# SCH_The-Weather-Station_2024-06-20.net
KiCad netlist of a schematic drawn in EasyEDA
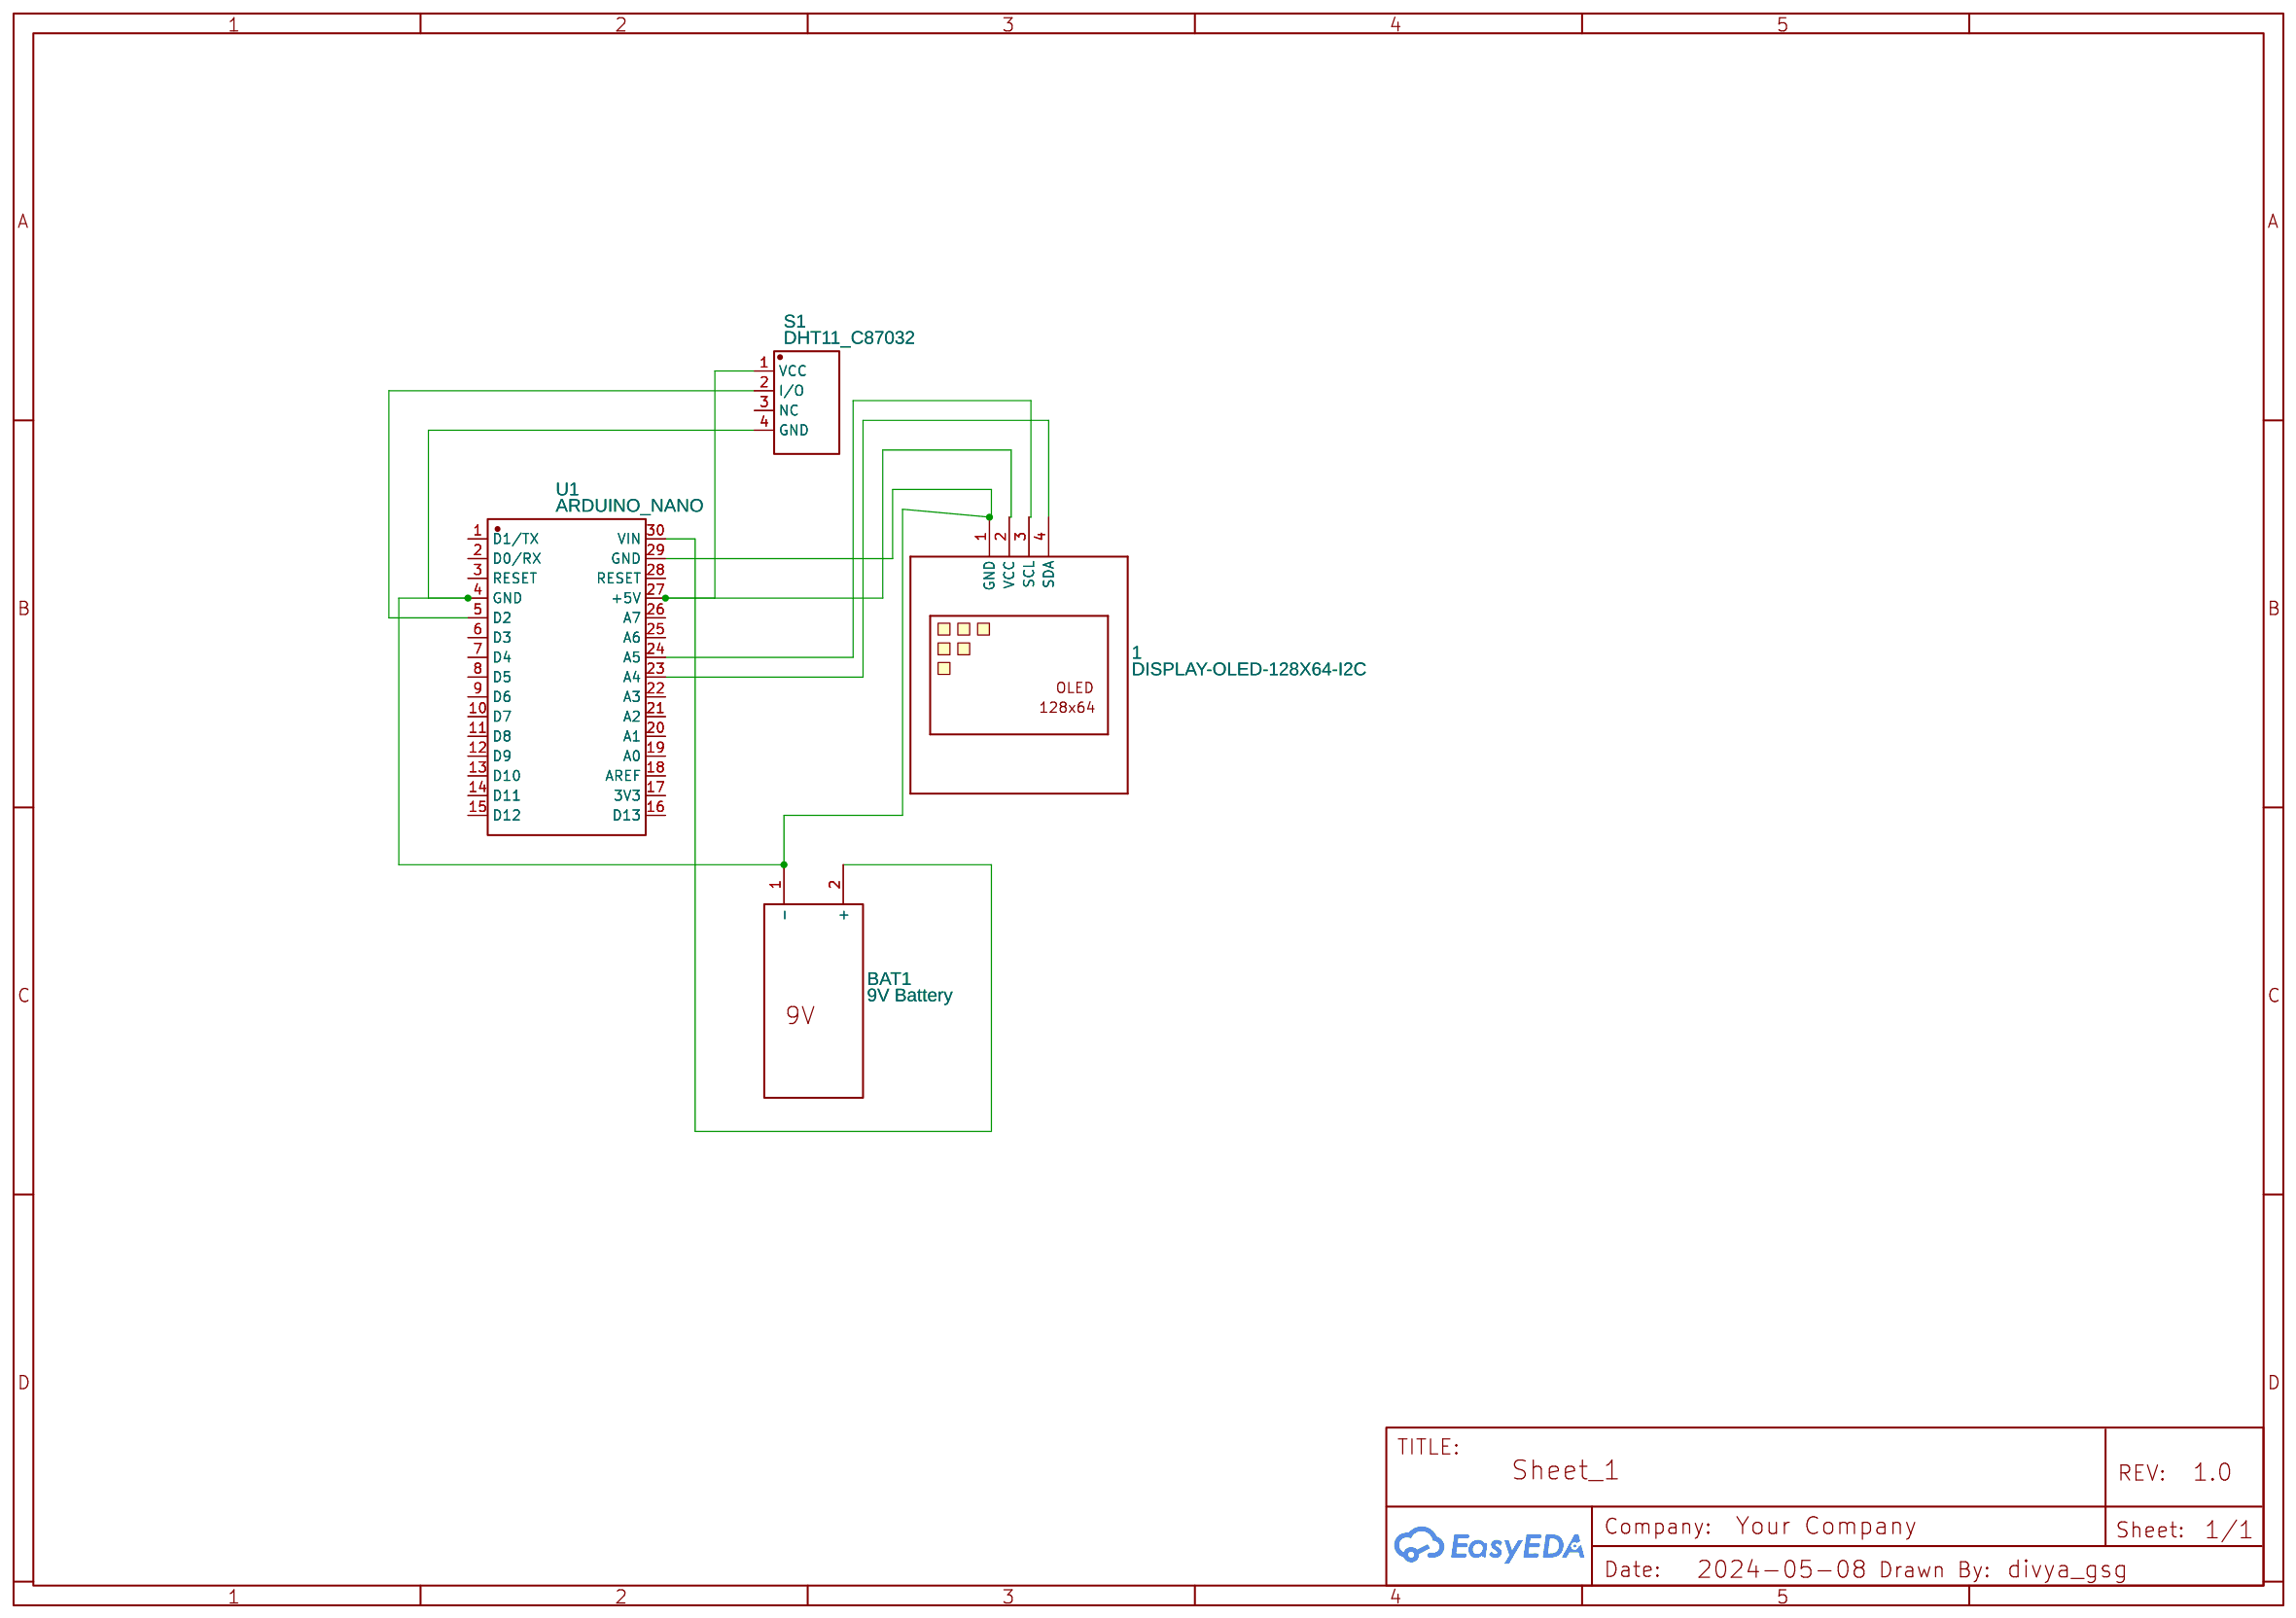
[diagram p0: schematic sheet]

(export (version "E")
  (design (tool "Eeschema 10.0.6"))
  (components
    (comp (ref "1") (value "DISPLAY-OLED-128X64-I2C") (libsource (lib "") (part "DISPLAY-OLED-128X64-I2C")))
    (comp (ref "BAT1") (value "9V Battery") (libsource (lib "") (part "9V Battery")))
    (comp (ref "S1")
      (value "DHT11_C87032")
      (fields (field (name "Manufacturer Part") "DHT11") (field (name "Manufacturer") "AOSONG"))
      (libsource (lib "") (part "DHT11_C87032"))
    )
    (comp (ref "U1") (value "ARDUINO_NANO") (libsource (lib "") (part "ARDUINO_NANO")))
  )
  (nets
    (net (code "1") (name "Net-(1-GND)") (class "Default")
      (node (ref "1") (pin "1") (pinfunction "GND_1") (pintype "bidirectional"))
      (node (ref "BAT1") (pin "1") (pinfunction "-_1") (pintype "unspecified"))
      (node (ref "S1") (pin "4") (pinfunction "GND_4") (pintype "unspecified"))
      (node (ref "U1") (pin "29") (pinfunction "GND_29") (pintype "unspecified"))
      (node (ref "U1") (pin "4") (pinfunction "GND_4") (pintype "unspecified"))
    )
    (net (code "2") (name "Net-(1-SCL)") (class "Default")
      (node (ref "1") (pin "3") (pinfunction "SCL_3") (pintype "bidirectional"))
      (node (ref "U1") (pin "24") (pinfunction "A5_24") (pintype "unspecified"))
    )
    (net (code "3") (name "Net-(1-SDA)") (class "Default")
      (node (ref "1") (pin "4") (pinfunction "SDA_4") (pintype "bidirectional"))
      (node (ref "U1") (pin "23") (pinfunction "A4_23") (pintype "unspecified"))
    )
    (net (code "4") (name "Net-(1-VCC)") (class "Default")
      (node (ref "1") (pin "2") (pinfunction "VCC_2") (pintype "bidirectional"))
      (node (ref "S1") (pin "1") (pinfunction "VCC_1") (pintype "unspecified"))
      (node (ref "U1") (pin "27") (pinfunction "+5V_27") (pintype "unspecified"))
    )
    (net (code "5") (name "Net-(BAT1-+)") (class "Default")
      (node (ref "BAT1") (pin "2") (pinfunction "+_2") (pintype "unspecified"))
      (node (ref "U1") (pin "30") (pinfunction "VIN_30") (pintype "unspecified"))
    )
    (net (code "6") (name "Net-(S1-I{slash}O)") (class "Default")
      (node (ref "S1") (pin "2") (pinfunction "I/O_2") (pintype "unspecified"))
      (node (ref "U1") (pin "5") (pinfunction "D2_5") (pintype "unspecified"))
    )
    (net (code "7") (name "unconnected-(S1-NC-Pad3)") (class "Default")
      (node (ref "S1") (pin "3") (pinfunction "NC_3") (pintype "unspecified"))
    )
    (net (code "8") (name "unconnected-(U1-3V3-Pad17)") (class "Default")
      (node (ref "U1") (pin "17") (pinfunction "3V3_17") (pintype "unspecified"))
    )
    (net (code "9") (name "unconnected-(U1-A0-Pad19)") (class "Default")
      (node (ref "U1") (pin "19") (pinfunction "A0_19") (pintype "unspecified"))
    )
    (net (code "10") (name "unconnected-(U1-A1-Pad20)") (class "Default")
      (node (ref "U1") (pin "20") (pinfunction "A1_20") (pintype "unspecified"))
    )
    (net (code "11") (name "unconnected-(U1-A2-Pad21)") (class "Default")
      (node (ref "U1") (pin "21") (pinfunction "A2_21") (pintype "unspecified"))
    )
    (net (code "12") (name "unconnected-(U1-A3-Pad22)") (class "Default")
      (node (ref "U1") (pin "22") (pinfunction "A3_22") (pintype "unspecified"))
    )
    (net (code "13") (name "unconnected-(U1-A6-Pad25)") (class "Default")
      (node (ref "U1") (pin "25") (pinfunction "A6_25") (pintype "unspecified"))
    )
    (net (code "14") (name "unconnected-(U1-A7-Pad26)") (class "Default")
      (node (ref "U1") (pin "26") (pinfunction "A7_26") (pintype "unspecified"))
    )
    (net (code "15") (name "unconnected-(U1-AREF-Pad18)") (class "Default")
      (node (ref "U1") (pin "18") (pinfunction "AREF_18") (pintype "unspecified"))
    )
    (net (code "16") (name "unconnected-(U1-D0{slash}RX-Pad2)") (class "Default")
      (node (ref "U1") (pin "2") (pinfunction "D0/RX_2") (pintype "unspecified"))
    )
    (net (code "17") (name "unconnected-(U1-D1{slash}TX-Pad1)") (class "Default")
      (node (ref "U1") (pin "1") (pinfunction "D1/TX_1") (pintype "unspecified"))
    )
    (net (code "18") (name "unconnected-(U1-D3-Pad6)") (class "Default")
      (node (ref "U1") (pin "6") (pinfunction "D3_6") (pintype "unspecified"))
    )
    (net (code "19") (name "unconnected-(U1-D4-Pad7)") (class "Default")
      (node (ref "U1") (pin "7") (pinfunction "D4_7") (pintype "unspecified"))
    )
    (net (code "20") (name "unconnected-(U1-D5-Pad8)") (class "Default")
      (node (ref "U1") (pin "8") (pinfunction "D5_8") (pintype "unspecified"))
    )
    (net (code "21") (name "unconnected-(U1-D6-Pad9)") (class "Default")
      (node (ref "U1") (pin "9") (pinfunction "D6_9") (pintype "unspecified"))
    )
    (net (code "22") (name "unconnected-(U1-D7-Pad10)") (class "Default")
      (node (ref "U1") (pin "10") (pinfunction "D7_10") (pintype "unspecified"))
    )
    (net (code "23") (name "unconnected-(U1-D8-Pad11)") (class "Default")
      (node (ref "U1") (pin "11") (pinfunction "D8_11") (pintype "unspecified"))
    )
    (net (code "24") (name "unconnected-(U1-D9-Pad12)") (class "Default")
      (node (ref "U1") (pin "12") (pinfunction "D9_12") (pintype "unspecified"))
    )
    (net (code "25") (name "unconnected-(U1-D10-Pad13)") (class "Default")
      (node (ref "U1") (pin "13") (pinfunction "D10_13") (pintype "unspecified"))
    )
    (net (code "26") (name "unconnected-(U1-D11-Pad14)") (class "Default")
      (node (ref "U1") (pin "14") (pinfunction "D11_14") (pintype "unspecified"))
    )
    (net (code "27") (name "unconnected-(U1-D12-Pad15)") (class "Default")
      (node (ref "U1") (pin "15") (pinfunction "D12_15") (pintype "unspecified"))
    )
    (net (code "28") (name "unconnected-(U1-D13-Pad16)") (class "Default")
      (node (ref "U1") (pin "16") (pinfunction "D13_16") (pintype "unspecified"))
    )
    (net (code "29") (name "unconnected-(U1-RESET-Pad3)") (class "Default")
      (node (ref "U1") (pin "3") (pinfunction "RESET_3") (pintype "unspecified"))
    )
    (net (code "30") (name "unconnected-(U1-RESET-Pad28)") (class "Default")
      (node (ref "U1") (pin "28") (pinfunction "RESET_28") (pintype "unspecified"))
    )
  )
)
